# CONTROLLER.net
KiCad netlist of a schematic drawn in Altium Designer
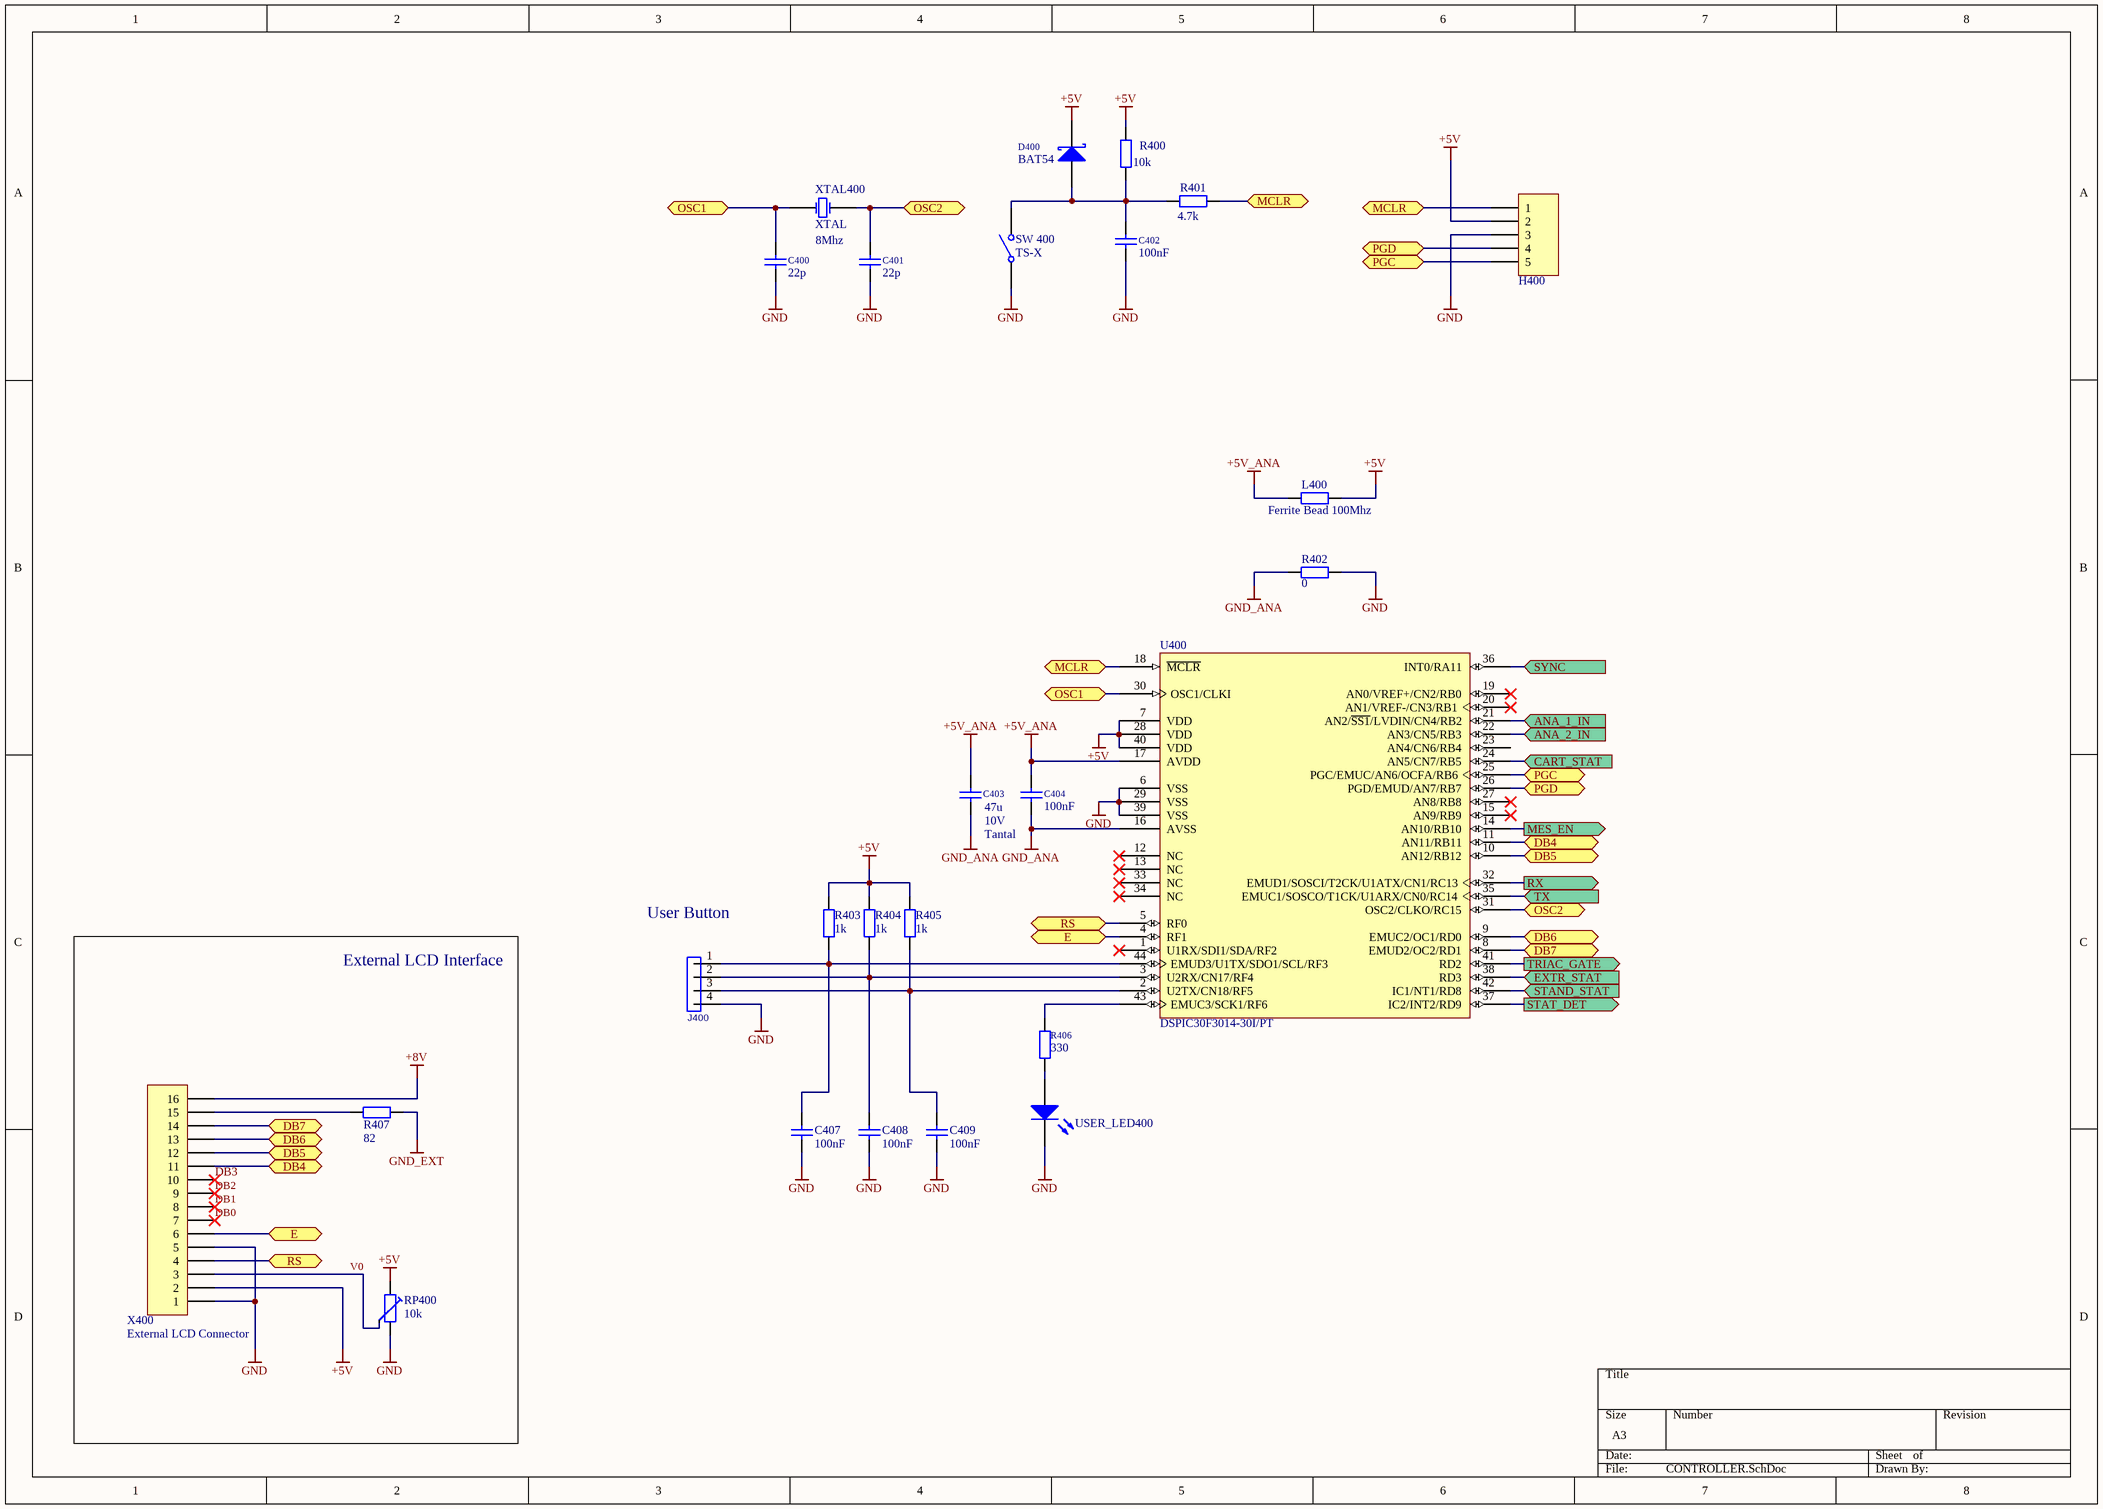
[diagram p0: CONTROLLER.SchDoc]

(export (version "E")
  (design (tool "Eeschema 10.0.6"))
  (components
    (comp (ref "C400")
      (value "22p")
      (footprint "3216[1206]")
      (fields (field (name "Comment") "Cap"))
      (libsource (lib "Capacitors") (part "Cap"))
    )
    (comp (ref "C401")
      (value "22p")
      (footprint "3216[1206]")
      (fields (field (name "Comment") "Cap"))
      (libsource (lib "Capacitors") (part "Cap"))
    )
    (comp (ref "C402")
      (value "100nF")
      (footprint "3216[1206]")
      (fields (field (name "Comment") "Cap"))
      (libsource (lib "Capacitors") (part "Cap"))
    )
    (comp (ref "C403")
      (value "47u")
      (footprint "3216[1206]")
      (fields (field (name "VOLTAGE") "10V") (field (name "TYPE") "Tantal") (field (name "Comment") "Cap"))
      (libsource (lib "Capacitors") (part "Cap"))
    )
    (comp (ref "C404")
      (value "100nF")
      (footprint "3216[1206]")
      (fields (field (name "Comment") "Cap"))
      (libsource (lib "Capacitors") (part "Cap"))
    )
    (comp (ref "C407")
      (value "100nF")
      (footprint "3216[1206]")
      (fields (field (name "Comment") "Cap 1206"))
      (libsource (lib "Capacitors") (part "Cap 1206"))
    )
    (comp (ref "C408")
      (value "100nF")
      (footprint "3216[1206]")
      (fields (field (name "Comment") "Cap 1206"))
      (libsource (lib "Capacitors") (part "Cap 1206"))
    )
    (comp (ref "C409")
      (value "100nF")
      (footprint "3216[1206]")
      (fields (field (name "Comment") "Cap 1206"))
      (libsource (lib "Capacitors") (part "Cap 1206"))
    )
    (comp (ref "D400") (value "BAT54") (footprint "SOT23") (libsource (lib "diode") (part "BAT54")))
    (comp (ref "H400")
      (value "HEADER X5")
      (footprint "SIP5")
      (libsource (lib "Connector") (part "HEADER X5"))
    )
    (comp (ref "J400") (value "SIP4") (footprint "SIP4") (libsource (lib "DMB20") (part "SIP4")))
    (comp (ref "L400")
      (value "Ferrite Bead 100Mhz")
      (footprint "3216[1206]")
      (fields (field (name "Comment") "RES"))
      (libsource (lib "") (part "RES 1_1"))
    )
    (comp (ref "R400")
      (value "10k")
      (footprint "3216[1206]")
      (fields (field (name "Comment") "RES"))
      (libsource (lib "") (part "RES 1_2"))
    )
    (comp (ref "R401")
      (value "4.7k")
      (footprint "3216[1206]")
      (fields (field (name "Comment") "RES"))
      (libsource (lib "") (part "RES 1_1"))
    )
    (comp (ref "R402")
      (value "0")
      (footprint "3216[1206]")
      (fields (field (name "Comment") "RES"))
      (libsource (lib "") (part "RES 1_1"))
    )
    (comp (ref "R403")
      (value "1k")
      (footprint "3216[1206]")
      (fields (field (name "Comment") "RES"))
      (libsource (lib "Resistor") (part "RES 1"))
    )
    (comp (ref "R404")
      (value "1k")
      (footprint "3216[1206]")
      (fields (field (name "Comment") "RES"))
      (libsource (lib "Resistor") (part "RES 1"))
    )
    (comp (ref "R405")
      (value "1k")
      (footprint "3216[1206]")
      (fields (field (name "Comment") "RES"))
      (libsource (lib "Resistor") (part "RES 1"))
    )
    (comp (ref "R406")
      (value "330")
      (footprint "3216[1206]")
      (fields (field (name "Comment") "Resistor"))
      (libsource (lib "Resistor") (part "RES1"))
    )
    (comp (ref "R407")
      (value "82")
      (footprint "1206_REFLOW")
      (fields (field (name "Comment") "RES"))
      (libsource (lib "") (part "RES 1_1"))
    )
    (comp (ref "RP400")
      (value "10k")
      (footprint "BOURNS3296W")
      (fields (field (name "Comment") "Trimmer"))
      (libsource (lib "Resistor") (part "Res Trim"))
    )
    (comp (ref "SW 400")
      (value "TS-X")
      (footprint "TS Button")
      (fields (field (name "Comment") "Tack Button 6x6"))
      (libsource (lib "Button") (part "TS-X Button"))
    )
    (comp (ref "U400")
      (value "DSPIC30F3014-30I/PT")
      (footprint "TQFP-PT44_M")
      (fields (field (name "PUBLISHER") "Altium Limited"))
      (libsource (lib "Microchip DSC 16-Bit dsPIC30F") (part "DSPIC30F3014-30I/PT"))
    )
    (comp (ref "USER_LED400") (value "LED") (footprint "LED_1206") (libsource (lib "LED") (part "LED")))
    (comp (ref "X400")
      (value "HEADER X16")
      (footprint "HDR1X16")
      (libsource (lib "Connector") (part "HEADER X16"))
    )
    (comp (ref "XTAL400")
      (value "XTAL")
      (footprint "XTAL")
      (fields (field (name "ALTIUM_VALUE") "8Mhz"))
      (libsource (lib "Oscillator") (part "XTAL"))
    )
  )
  (nets
    (net (code "1") (name "+5V") (class "Default")
      (node (ref "D400") (pin "3") (pinfunction "K_3") (pintype "passive"))
      (node (ref "H400") (pin "2") (pinfunction "2_2") (pintype "passive"))
      (node (ref "L400") (pin "2") (pinfunction "2_2") (pintype "passive"))
      (node (ref "R400") (pin "1") (pinfunction "1_1") (pintype "passive"))
      (node (ref "R403") (pin "2") (pinfunction "2_2") (pintype "passive"))
      (node (ref "R404") (pin "2") (pinfunction "2_2") (pintype "passive"))
      (node (ref "R405") (pin "2") (pinfunction "2_2") (pintype "passive"))
      (node (ref "RP400") (pin "3") (pinfunction "3_3") (pintype "passive"))
      (node (ref "U400") (pin "28") (pinfunction "VDD_28") (pintype "power_in"))
      (node (ref "U400") (pin "40") (pinfunction "VDD_40") (pintype "power_in"))
      (node (ref "U400") (pin "7") (pinfunction "VDD_7") (pintype "power_in"))
      (node (ref "X400") (pin "2") (pinfunction "2_2") (pintype "passive"))
    )
    (net (code "2") (name "+5V_ANA") (class "Default")
      (node (ref "C403") (pin "2") (pinfunction "2_2") (pintype "passive"))
      (node (ref "C404") (pin "2") (pinfunction "2_2") (pintype "passive"))
      (node (ref "L400") (pin "1") (pinfunction "1_1") (pintype "passive"))
      (node (ref "U400") (pin "17") (pinfunction "AVDD_17") (pintype "power_in"))
    )
    (net (code "3") (name "+8V") (class "Default")
      (node (ref "X400") (pin "16") (pinfunction "16_16") (pintype "passive"))
    )
    (net (code "4") (name "/ANA_1_IN") (class "Default")
      (node (ref "U400") (pin "21") (pinfunction "AN2/~{SS1}/LVDIN/CN4/RB2_21") (pintype "bidirectional"))
    )
    (net (code "5") (name "/ANA_2_IN") (class "Default")
      (node (ref "U400") (pin "22") (pinfunction "AN3/CN5/RB3_22") (pintype "bidirectional"))
    )
    (net (code "6") (name "/CART_STAT") (class "Default")
      (node (ref "U400") (pin "24") (pinfunction "AN5/CN7/RB5_24") (pintype "bidirectional"))
    )
    (net (code "7") (name "/DB0") (class "Default")
      (node (ref "X400") (pin "7") (pinfunction "7_7") (pintype "passive+no_connect"))
    )
    (net (code "8") (name "/DB1") (class "Default")
      (node (ref "X400") (pin "8") (pinfunction "8_8") (pintype "passive+no_connect"))
    )
    (net (code "9") (name "/DB2") (class "Default")
      (node (ref "X400") (pin "9") (pinfunction "9_9") (pintype "passive+no_connect"))
    )
    (net (code "10") (name "/DB3") (class "Default")
      (node (ref "X400") (pin "10") (pinfunction "10_10") (pintype "passive+no_connect"))
    )
    (net (code "11") (name "/DB4") (class "Default")
      (node (ref "U400") (pin "11") (pinfunction "AN11/RB11_11") (pintype "bidirectional"))
      (node (ref "X400") (pin "11") (pinfunction "11_11") (pintype "passive"))
    )
    (net (code "12") (name "/DB5") (class "Default")
      (node (ref "U400") (pin "10") (pinfunction "AN12/RB12_10") (pintype "bidirectional"))
      (node (ref "X400") (pin "12") (pinfunction "12_12") (pintype "passive"))
    )
    (net (code "13") (name "/DB6") (class "Default")
      (node (ref "U400") (pin "9") (pinfunction "EMUC2/OC1/RD0_9") (pintype "bidirectional"))
      (node (ref "X400") (pin "13") (pinfunction "13_13") (pintype "passive"))
    )
    (net (code "14") (name "/DB7") (class "Default")
      (node (ref "U400") (pin "8") (pinfunction "EMUD2/OC2/RD1_8") (pintype "bidirectional"))
      (node (ref "X400") (pin "14") (pinfunction "14_14") (pintype "passive"))
    )
    (net (code "15") (name "/E") (class "Default")
      (node (ref "U400") (pin "4") (pinfunction "RF1_4") (pintype "bidirectional"))
      (node (ref "X400") (pin "6") (pinfunction "6_6") (pintype "passive"))
    )
    (net (code "16") (name "/EXTR_STAT") (class "Default")
      (node (ref "U400") (pin "38") (pinfunction "RD3_38") (pintype "bidirectional"))
    )
    (net (code "17") (name "/MCLR") (class "Default")
      (node (ref "H400") (pin "1") (pinfunction "1_1") (pintype "passive"))
      (node (ref "R401") (pin "2") (pinfunction "2_2") (pintype "passive"))
      (node (ref "U400") (pin "18") (pinfunction "~{MCLR}_18") (pintype "input"))
    )
    (net (code "18") (name "/MES_EN") (class "Default")
      (node (ref "U400") (pin "14") (pinfunction "AN10/RB10_14") (pintype "bidirectional"))
    )
    (net (code "19") (name "/OSC1") (class "Default")
      (node (ref "C400") (pin "2") (pinfunction "2_2") (pintype "passive"))
      (node (ref "U400") (pin "30") (pinfunction "OSC1/CLKI_30") (pintype "input"))
      (node (ref "XTAL400") (pin "1") (pinfunction "OSC1_1") (pintype "passive"))
    )
    (net (code "20") (name "/OSC2") (class "Default")
      (node (ref "C401") (pin "2") (pinfunction "2_2") (pintype "passive"))
      (node (ref "U400") (pin "31") (pinfunction "OSC2/CLKO/RC15_31") (pintype "bidirectional"))
      (node (ref "XTAL400") (pin "2") (pinfunction "OSC2_2") (pintype "passive"))
    )
    (net (code "21") (name "/PGC") (class "Default")
      (node (ref "H400") (pin "5") (pinfunction "5_5") (pintype "passive"))
      (node (ref "U400") (pin "25") (pinfunction "PGC/EMUC/AN6/OCFA/RB6_25") (pintype "bidirectional"))
    )
    (net (code "22") (name "/PGD") (class "Default")
      (node (ref "H400") (pin "4") (pinfunction "4_4") (pintype "passive"))
      (node (ref "U400") (pin "26") (pinfunction "PGD/EMUD/AN7/RB7_26") (pintype "bidirectional"))
    )
    (net (code "23") (name "/RS") (class "Default")
      (node (ref "U400") (pin "5") (pinfunction "RF0_5") (pintype "bidirectional"))
      (node (ref "X400") (pin "4") (pinfunction "4_4") (pintype "passive"))
    )
    (net (code "24") (name "/RX") (class "Default")
      (node (ref "U400") (pin "32") (pinfunction "EMUD1/SOSCI/T2CK/U1ATX/CN1/RC13_32") (pintype "bidirectional"))
    )
    (net (code "25") (name "/STAND_STAT") (class "Default")
      (node (ref "U400") (pin "42") (pinfunction "IC1/NT1/RD8_42") (pintype "bidirectional"))
    )
    (net (code "26") (name "/STAT_DET") (class "Default")
      (node (ref "U400") (pin "37") (pinfunction "IC2/INT2/RD9_37") (pintype "bidirectional"))
    )
    (net (code "27") (name "/SYNC") (class "Default")
      (node (ref "U400") (pin "36") (pinfunction "INT0/RA11_36") (pintype "bidirectional"))
    )
    (net (code "28") (name "/TRIAC_GATE") (class "Default")
      (node (ref "U400") (pin "41") (pinfunction "RD2_41") (pintype "bidirectional"))
    )
    (net (code "29") (name "/TX") (class "Default")
      (node (ref "U400") (pin "35") (pinfunction "EMUC1/SOSCO/T1CK/U1ARX/CN0/RC14_35") (pintype "bidirectional"))
    )
    (net (code "30") (name "/V0") (class "Default")
      (node (ref "RP400") (pin "2") (pinfunction "2_2") (pintype "passive"))
      (node (ref "X400") (pin "3") (pinfunction "3_3") (pintype "passive"))
    )
    (net (code "31") (name "GND") (class "Default")
      (node (ref "C400") (pin "1") (pinfunction "1_1") (pintype "passive"))
      (node (ref "C401") (pin "1") (pinfunction "1_1") (pintype "passive"))
      (node (ref "C402") (pin "1") (pinfunction "1_1") (pintype "passive"))
      (node (ref "C407") (pin "1") (pinfunction "1_1") (pintype "passive"))
      (node (ref "C408") (pin "1") (pinfunction "1_1") (pintype "passive"))
      (node (ref "C409") (pin "1") (pinfunction "1_1") (pintype "passive"))
      (node (ref "H400") (pin "3") (pinfunction "3_3") (pintype "passive"))
      (node (ref "J400") (pin "4") (pintype "passive"))
      (node (ref "R402") (pin "2") (pinfunction "2_2") (pintype "passive"))
      (node (ref "RP400") (pin "1") (pinfunction "1_1") (pintype "passive"))
      (node (ref "SW 400") (pin "1") (pinfunction "COMMON_1") (pintype "passive"))
      (node (ref "U400") (pin "29") (pinfunction "VSS_29") (pintype "power_in"))
      (node (ref "U400") (pin "39") (pinfunction "VSS_39") (pintype "power_in"))
      (node (ref "U400") (pin "6") (pinfunction "VSS_6") (pintype "power_in"))
      (node (ref "USER_LED400") (pin "K") (pinfunction "K_K") (pintype "passive"))
      (node (ref "X400") (pin "1") (pinfunction "1_1") (pintype "passive"))
      (node (ref "X400") (pin "5") (pinfunction "5_5") (pintype "passive"))
    )
    (net (code "32") (name "GND_ANA") (class "Default")
      (node (ref "C403") (pin "1") (pinfunction "1_1") (pintype "passive"))
      (node (ref "C404") (pin "1") (pinfunction "1_1") (pintype "passive"))
      (node (ref "R402") (pin "1") (pinfunction "1_1") (pintype "passive"))
      (node (ref "U400") (pin "16") (pinfunction "AVSS_16") (pintype "power_in"))
    )
    (net (code "33") (name "GND_EXT") (class "Default")
      (node (ref "R407") (pin "2") (pinfunction "2_2") (pintype "passive"))
    )
    (net (code "34") (name "Net-(D400-A)") (class "Default")
      (node (ref "C402") (pin "2") (pinfunction "2_2") (pintype "passive"))
      (node (ref "D400") (pin "1") (pinfunction "A_1") (pintype "passive"))
      (node (ref "R400") (pin "2") (pinfunction "2_2") (pintype "passive"))
      (node (ref "R401") (pin "1") (pinfunction "1_1") (pintype "passive"))
      (node (ref "SW 400") (pin "4") (pinfunction "NO_4") (pintype "passive"))
    )
    (net (code "35") (name "Net-(R406-Pad2)") (class "Default")
      (node (ref "R406") (pin "2") (pinfunction "2_2") (pintype "passive"))
      (node (ref "USER_LED400") (pin "A") (pinfunction "A_A") (pintype "passive"))
    )
    (net (code "36") (name "Net-(R407-Pad1)") (class "Default")
      (node (ref "R407") (pin "1") (pinfunction "1_1") (pintype "passive"))
      (node (ref "X400") (pin "15") (pinfunction "15_15") (pintype "passive"))
    )
    (net (code "37") (name "Net-(U400-EMUC3{slash}SCK1{slash}RF6)") (class "Default")
      (node (ref "R406") (pin "1") (pinfunction "1_1") (pintype "passive"))
      (node (ref "U400") (pin "43") (pinfunction "EMUC3/SCK1/RF6_43") (pintype "bidirectional"))
    )
    (net (code "38") (name "Net-(U400-EMUD3{slash}U1TX{slash}SDO1{slash}SCL{slash}RF3)") (class "Default")
      (node (ref "C407") (pin "2") (pinfunction "2_2") (pintype "passive"))
      (node (ref "J400") (pin "1") (pintype "passive"))
      (node (ref "R403") (pin "1") (pinfunction "1_1") (pintype "passive"))
      (node (ref "U400") (pin "44") (pinfunction "EMUD3/U1TX/SDO1/SCL/RF3_44") (pintype "bidirectional"))
    )
    (net (code "39") (name "Net-(U400-U2RX{slash}CN17{slash}RF4)") (class "Default")
      (node (ref "C408") (pin "2") (pinfunction "2_2") (pintype "passive"))
      (node (ref "J400") (pin "2") (pintype "passive"))
      (node (ref "R404") (pin "1") (pinfunction "1_1") (pintype "passive"))
      (node (ref "U400") (pin "3") (pinfunction "U2RX/CN17/RF4_3") (pintype "bidirectional"))
    )
    (net (code "40") (name "Net-(U400-U2TX{slash}CN18{slash}RF5)") (class "Default")
      (node (ref "C409") (pin "2") (pinfunction "2_2") (pintype "passive"))
      (node (ref "J400") (pin "3") (pintype "passive"))
      (node (ref "R405") (pin "1") (pinfunction "1_1") (pintype "passive"))
      (node (ref "U400") (pin "2") (pinfunction "U2TX/CN18/RF5_2") (pintype "bidirectional"))
    )
    (net (code "41") (name "unconnected-(U400-AN0{slash}VREF+{slash}CN2{slash}RB0-Pad19)") (class "Default")
      (node (ref "U400") (pin "19") (pinfunction "AN0/VREF+/CN2/RB0_19") (pintype "bidirectional+no_connect"))
    )
    (net (code "42") (name "unconnected-(U400-AN1{slash}VREF-{slash}CN3{slash}RB1-Pad20)") (class "Default")
      (node (ref "U400") (pin "20") (pinfunction "AN1/VREF-/CN3/RB1_20") (pintype "bidirectional+no_connect"))
    )
    (net (code "43") (name "unconnected-(U400-AN4{slash}CN6{slash}RB4-Pad23)") (class "Default")
      (node (ref "U400") (pin "23") (pinfunction "AN4/CN6/RB4_23") (pintype "bidirectional"))
    )
    (net (code "44") (name "unconnected-(U400-AN8{slash}RB8-Pad27)") (class "Default")
      (node (ref "U400") (pin "27") (pinfunction "AN8/RB8_27") (pintype "bidirectional+no_connect"))
    )
    (net (code "45") (name "unconnected-(U400-AN9{slash}RB9-Pad15)") (class "Default")
      (node (ref "U400") (pin "15") (pinfunction "AN9/RB9_15") (pintype "bidirectional+no_connect"))
    )
    (net (code "46") (name "unconnected-(U400-NC-Pad12)") (class "Default")
      (node (ref "U400") (pin "12") (pinfunction "NC_12") (pintype "passive+no_connect"))
    )
    (net (code "47") (name "unconnected-(U400-NC-Pad13)") (class "Default")
      (node (ref "U400") (pin "13") (pinfunction "NC_13") (pintype "passive+no_connect"))
    )
    (net (code "48") (name "unconnected-(U400-NC-Pad33)") (class "Default")
      (node (ref "U400") (pin "33") (pinfunction "NC_33") (pintype "passive+no_connect"))
    )
    (net (code "49") (name "unconnected-(U400-NC-Pad34)") (class "Default")
      (node (ref "U400") (pin "34") (pinfunction "NC_34") (pintype "passive+no_connect"))
    )
    (net (code "50") (name "unconnected-(U400-U1RX{slash}SDI1{slash}SDA{slash}RF2-Pad1)") (class "Default")
      (node (ref "U400") (pin "1") (pinfunction "U1RX/SDI1/SDA/RF2_1") (pintype "bidirectional+no_connect"))
    )
  )
)
